# LP-IMP-P1_V3.net
KiCad netlist of a schematic drawn in EAGLE
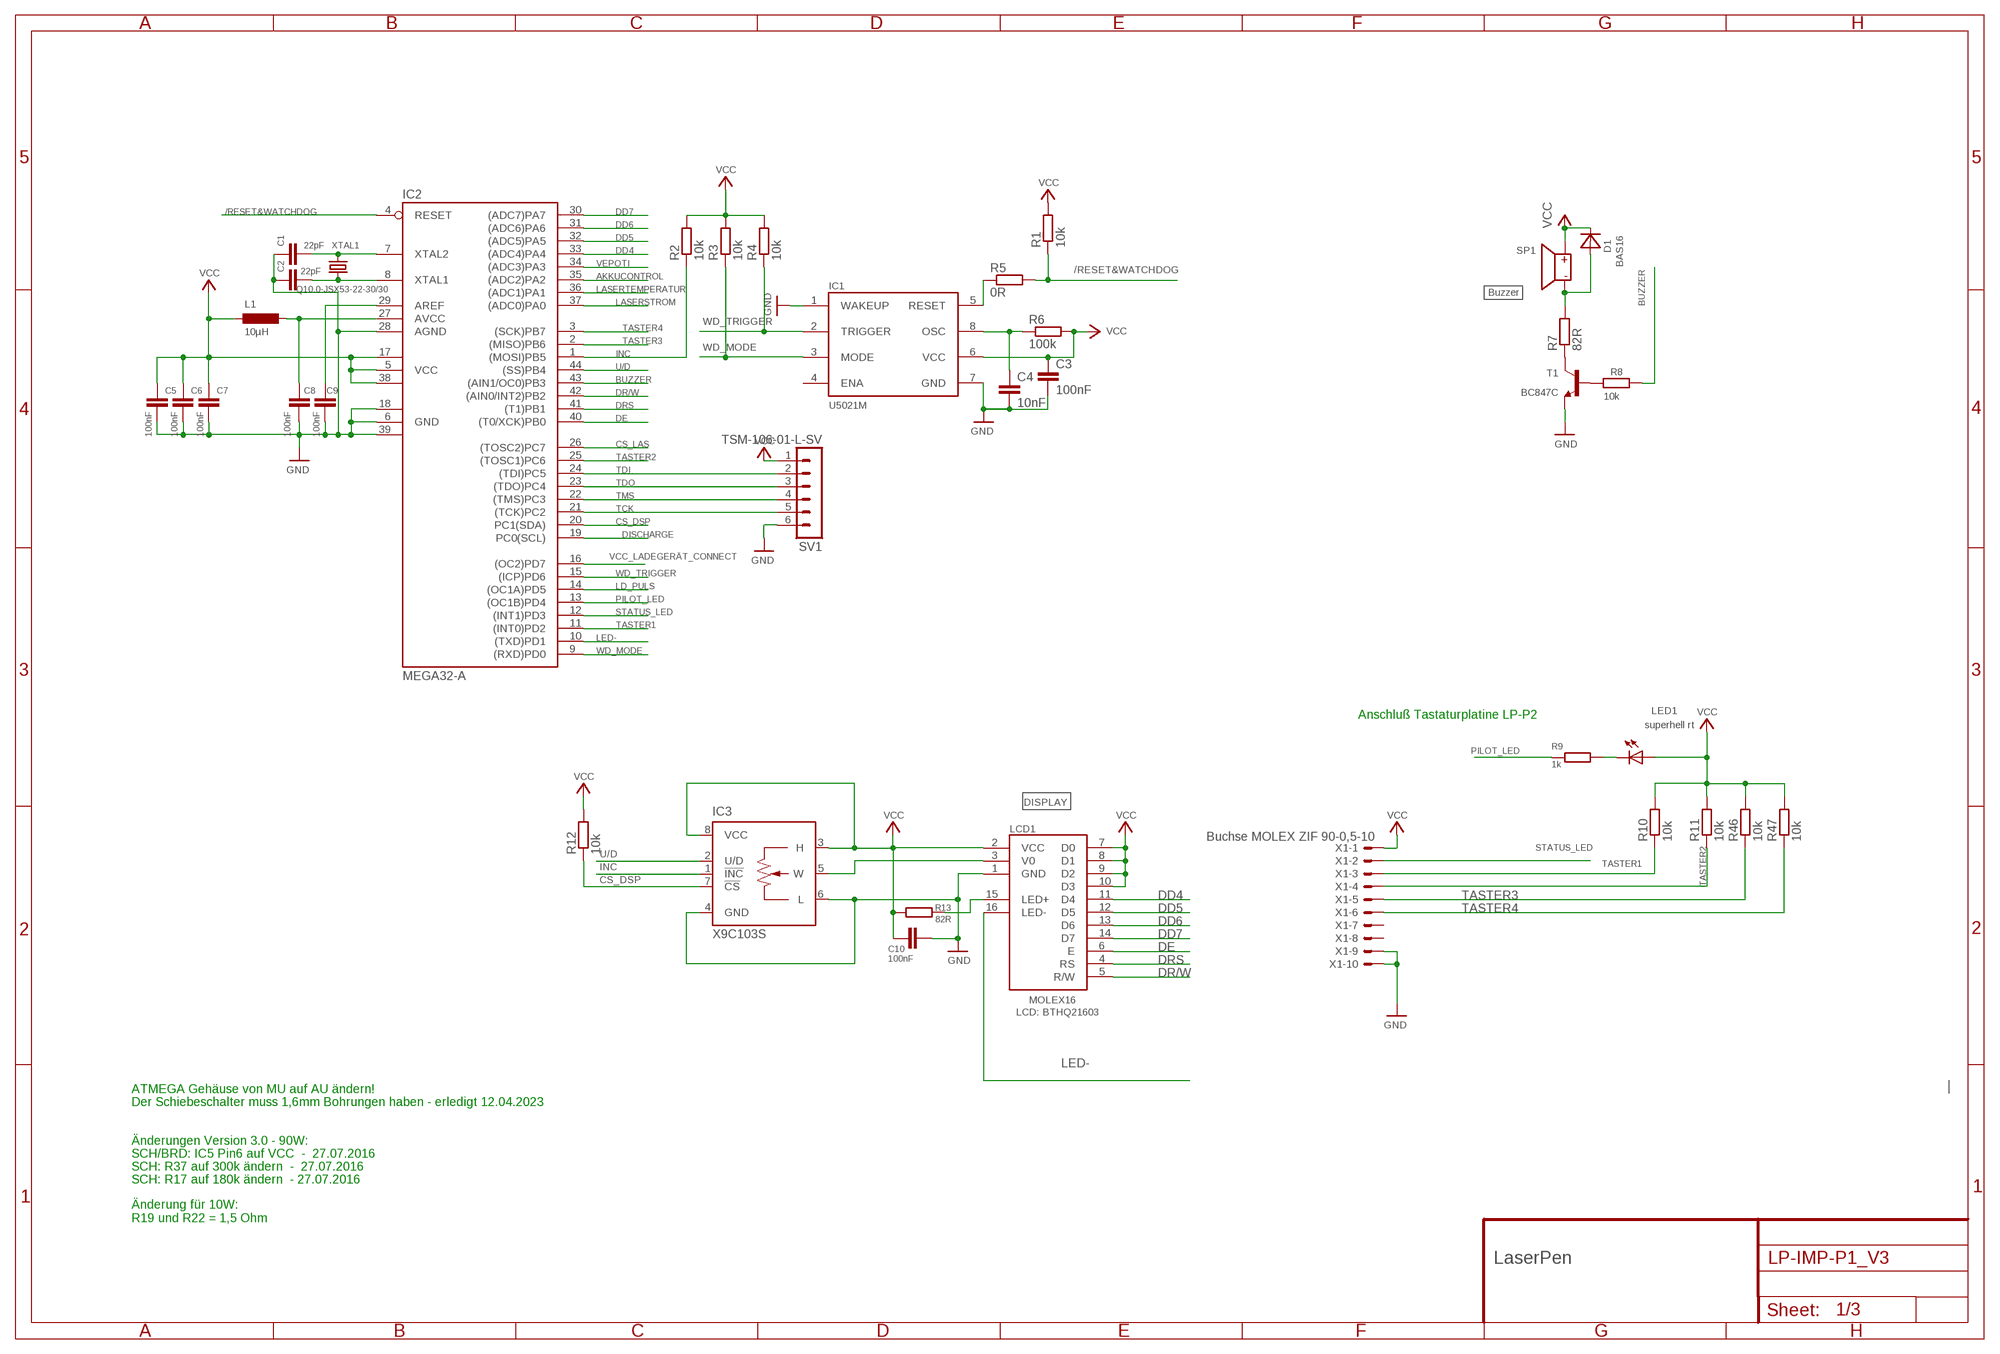
[diagram p0: schematic, sheet 1]
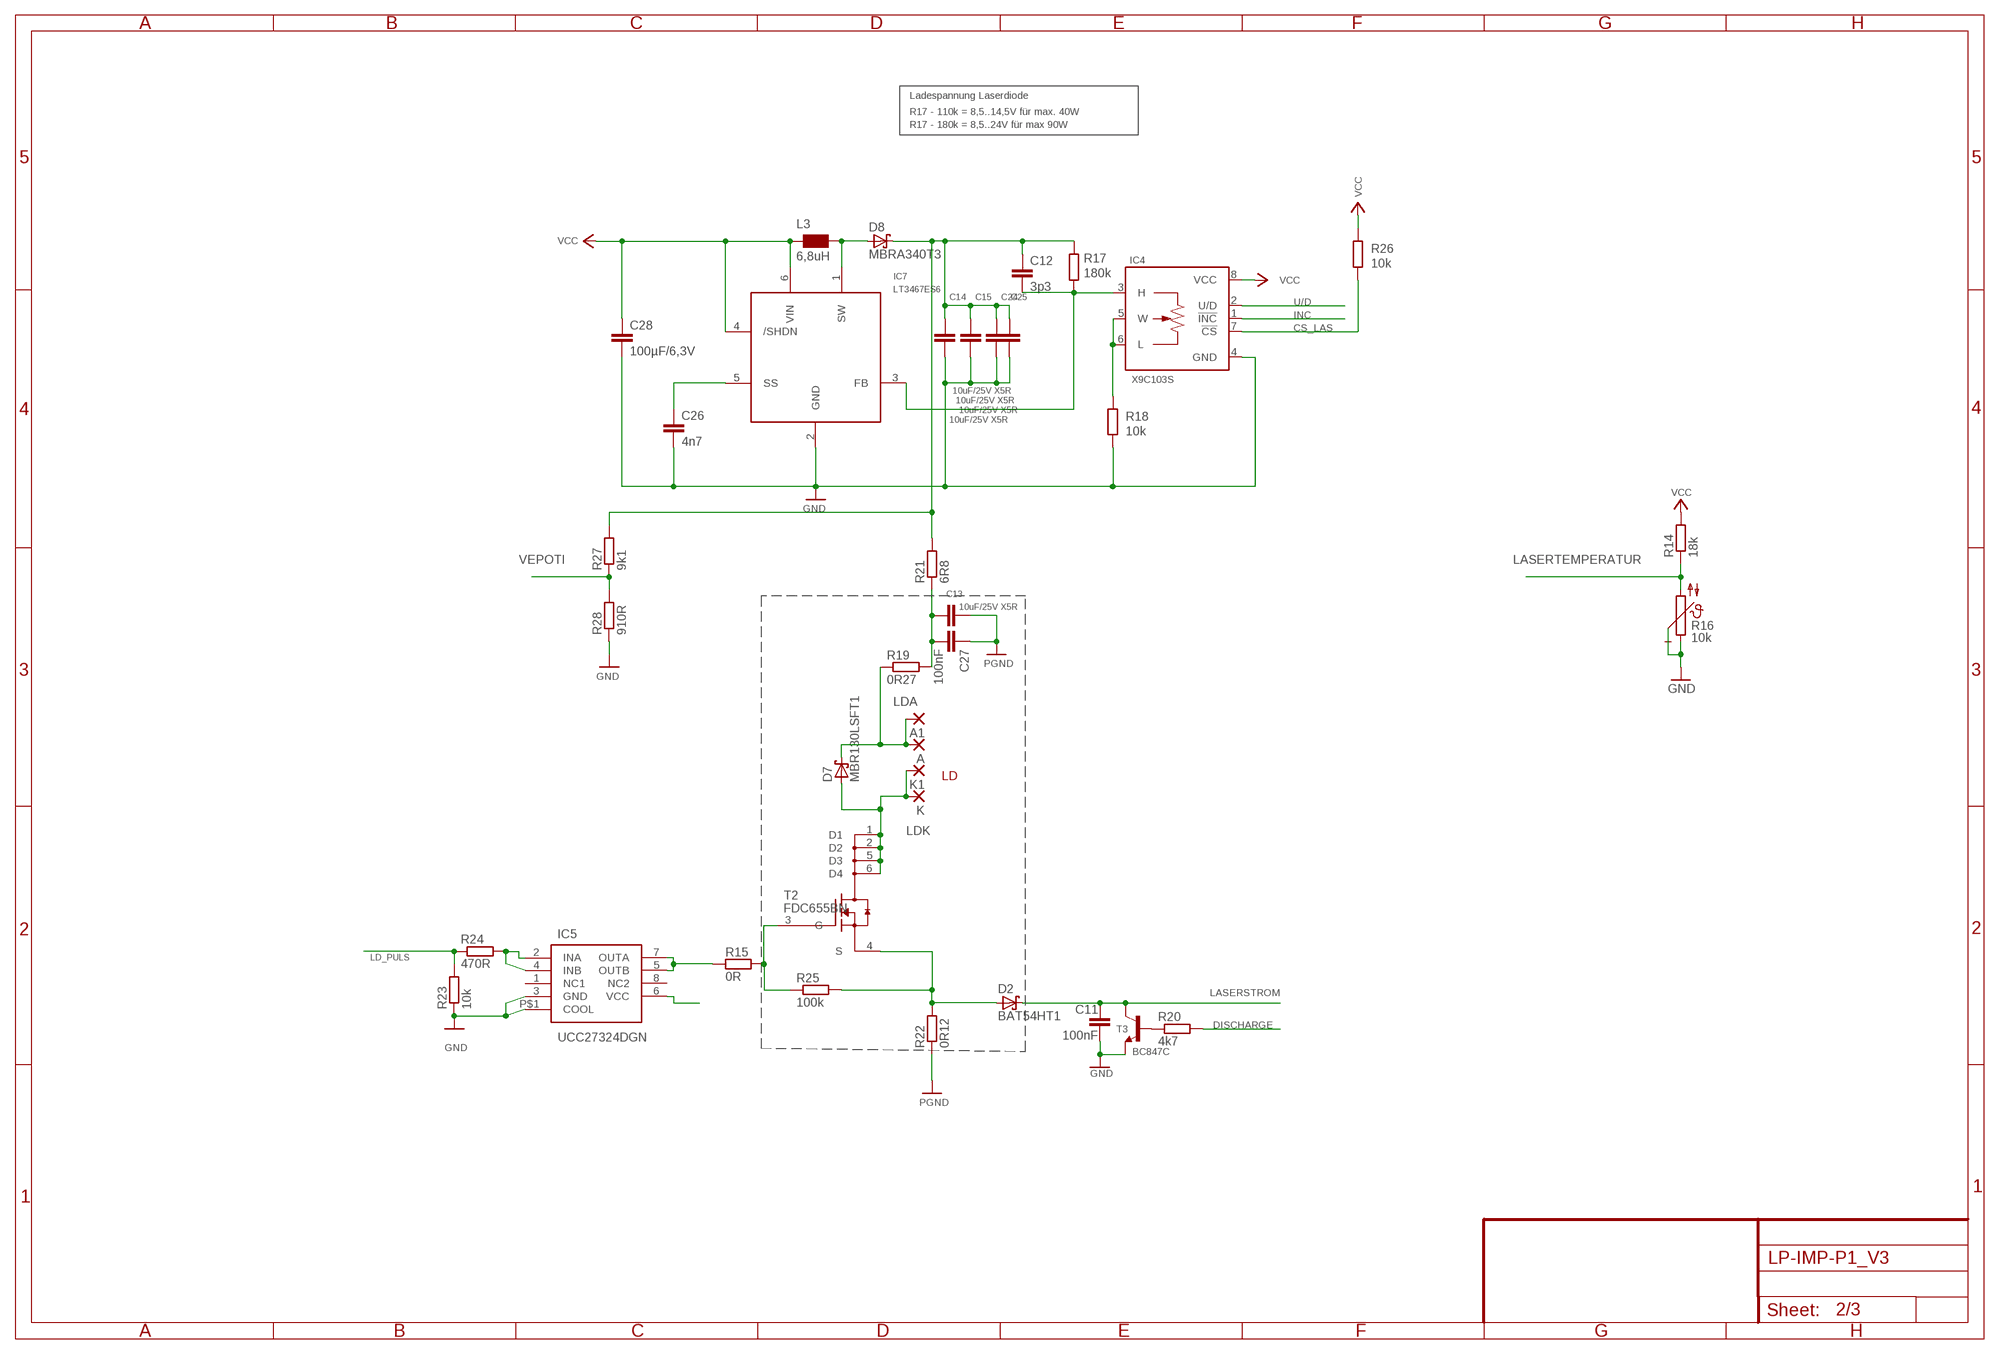
[diagram p1: schematic, sheet 2]
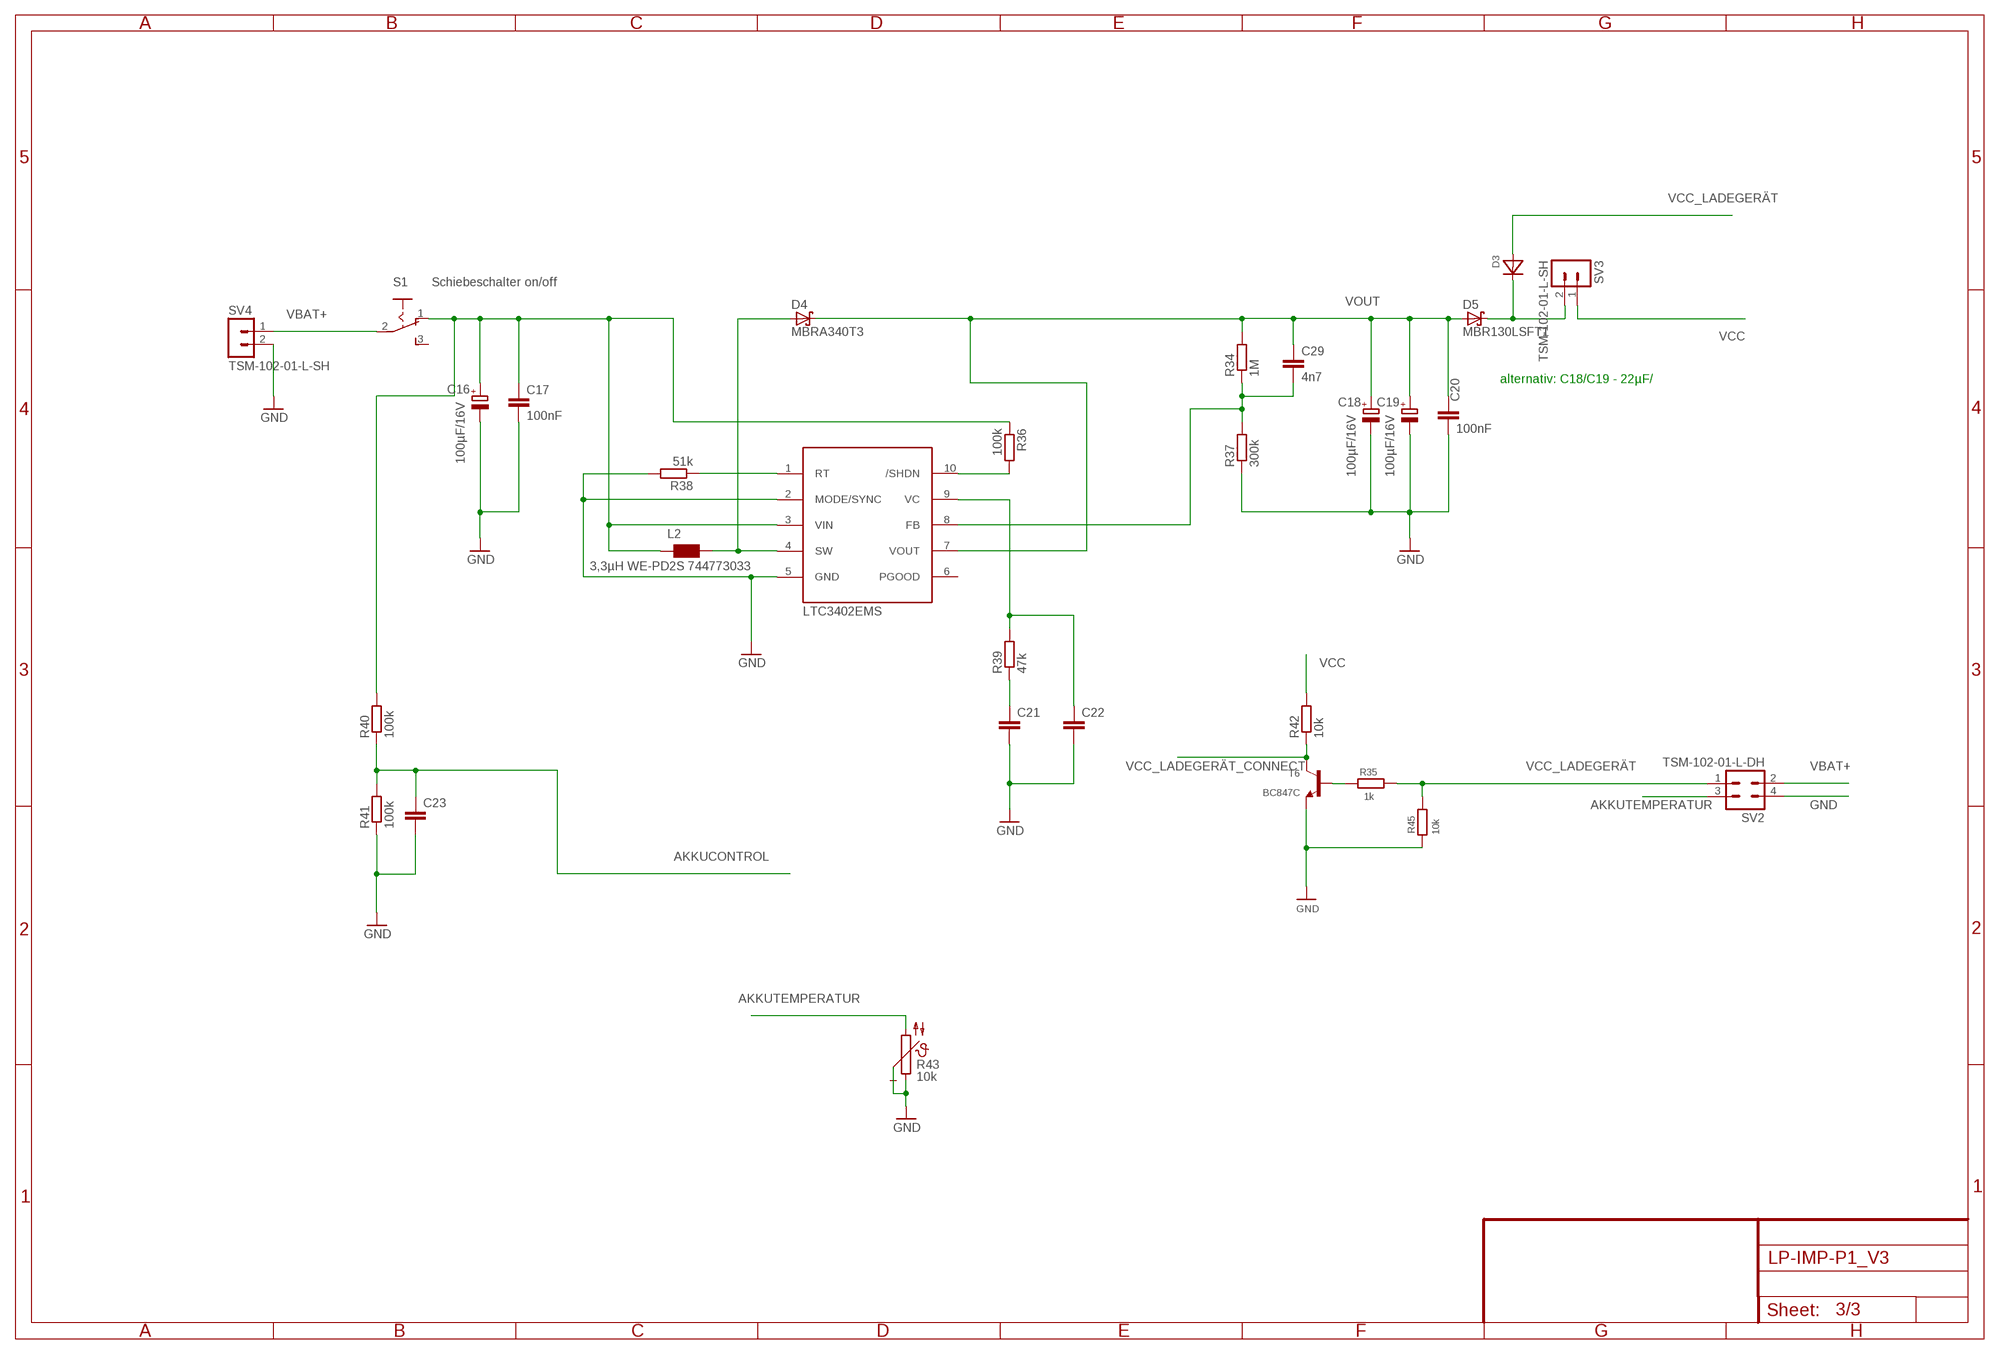
[diagram p2: schematic, sheet 3]

(export (version "E")
  (design (tool "Eeschema 10.0.6"))
  (components
    (comp (ref "A")
      (value "WIREPADSMD1,27-254")
      (footprint "eagle-import:SMD1,27-2,54")
      (libsource (lib "eagle-import") (part "WIREPADSMD1,27-254"))
    )
    (comp (ref "A1")
      (value "WIREPADSMD1,27-254")
      (footprint "eagle-import:SMD1,27-2,54")
      (libsource (lib "eagle-import") (part "WIREPADSMD1,27-254"))
    )
    (comp (ref "C11")
      (value "100nF")
      (footprint "eagle-import:C0603")
      (libsource (lib "eagle-import") (part "C-EUC0603"))
    )
    (comp (ref "C12")
      (value "3p3")
      (footprint "eagle-import:C0603")
      (libsource (lib "eagle-import") (part "C-EUC0603"))
    )
    (comp (ref "C13")
      (value "10uF/25V X5R")
      (footprint "eagle-import:C1210K")
      (libsource (lib "eagle-import") (part "C-EUC1210K"))
    )
    (comp (ref "C14")
      (value "10uF/25V X5R")
      (footprint "eagle-import:C1210K")
      (libsource (lib "eagle-import") (part "C-EUC1210K"))
    )
    (comp (ref "C15")
      (value "10uF/25V X5R")
      (footprint "eagle-import:C1210K")
      (libsource (lib "eagle-import") (part "C-EUC1210K"))
    )
    (comp (ref "C24")
      (value "10uF/25V X5R")
      (footprint "eagle-import:C1210K")
      (libsource (lib "eagle-import") (part "C-EUC1210K"))
    )
    (comp (ref "C25")
      (value "10uF/25V X5R")
      (footprint "eagle-import:C1210K")
      (libsource (lib "eagle-import") (part "C-EUC1210K"))
    )
    (comp (ref "C26")
      (value "4n7")
      (footprint "eagle-import:C0603K")
      (libsource (lib "eagle-import") (part "C-EUC0603K"))
    )
    (comp (ref "C27")
      (value "100nF")
      (footprint "eagle-import:C0603")
      (libsource (lib "eagle-import") (part "C-EUC0603"))
    )
    (comp (ref "C28")
      (value "100µF/6,3V")
      (footprint "eagle-import:C1210K")
      (libsource (lib "eagle-import") (part "C-EUC1210K"))
    )
    (comp (ref "D2")
      (value "BAT54HT1")
      (footprint "eagle-import:SOD-323")
      (libsource (lib "eagle-import") (part "BAT54HT1"))
    )
    (comp (ref "D7")
      (value "MBR130LSFT1")
      (footprint "eagle-import:SOD-123LF")
      (libsource (lib "eagle-import") (part "MBR130LSFT1"))
    )
    (comp (ref "D8")
      (value "MBRA340T3")
      (footprint "eagle-import:SMA")
      (libsource (lib "eagle-import") (part "pulslaser_MBRA340T3"))
    )
    (comp (ref "IC4")
      (value "X9C103S")
      (footprint "eagle-import:SOIC08")
      (libsource (lib "eagle-import") (part "X9C102S"))
    )
    (comp (ref "IC5")
      (value "UCC27324DGN")
      (footprint "eagle-import:R-PDSO-G8")
      (libsource (lib "eagle-import") (part "UCC27324DGN"))
    )
    (comp (ref "IC7")
      (value "LT3467ES6")
      (footprint "eagle-import:TSOT-23-6")
      (libsource (lib "eagle-import") (part "LT3467ES6"))
    )
    (comp (ref "K")
      (value "WIREPADSMD1,27-254")
      (footprint "eagle-import:SMD1,27-2,54")
      (libsource (lib "eagle-import") (part "WIREPADSMD1,27-254"))
    )
    (comp (ref "K1")
      (value "WIREPADSMD1,27-254")
      (footprint "eagle-import:SMD1,27-2,54")
      (libsource (lib "eagle-import") (part "WIREPADSMD1,27-254"))
    )
    (comp (ref "L3")
      (value "6,8uH")
      (footprint "eagle-import:WE-PD2_S")
      (libsource (lib "eagle-import") (part "WE-PD2_S"))
    )
    (comp (ref "R14")
      (value "18k")
      (footprint "eagle-import:R0603")
      (libsource (lib "eagle-import") (part "R-EU_R0603"))
    )
    (comp (ref "R15")
      (value "0R")
      (footprint "eagle-import:MINI_MELF-0204R")
      (libsource (lib "eagle-import") (part "R-EU_MELF0204R"))
    )
    (comp (ref "R16")
      (value "10k")
      (footprint "eagle-import:R0805")
      (libsource (lib "eagle-import") (part "NTC640SMD0805"))
    )
    (comp (ref "R17")
      (value "180k")
      (footprint "eagle-import:R0603")
      (libsource (lib "eagle-import") (part "R-EU_R0603"))
    )
    (comp (ref "R18")
      (value "10k")
      (footprint "eagle-import:R0603")
      (libsource (lib "eagle-import") (part "R-EU_R0603"))
    )
    (comp (ref "R19")
      (value "0R27")
      (footprint "eagle-import:MINI_MELF-0204R")
      (libsource (lib "eagle-import") (part "R-EU_MELF0204R"))
    )
    (comp (ref "R20")
      (value "4k7")
      (footprint "eagle-import:R0603")
      (libsource (lib "eagle-import") (part "R-EU_R0603"))
    )
    (comp (ref "R21")
      (value "6R8")
      (footprint "eagle-import:MINI_MELF-0204R")
      (libsource (lib "eagle-import") (part "R-EU_MELF0204R"))
    )
    (comp (ref "R22")
      (value "0R12")
      (footprint "eagle-import:MINI_MELF-0204R")
      (libsource (lib "eagle-import") (part "R-EU_MELF0204R"))
    )
    (comp (ref "R23")
      (value "10k")
      (footprint "eagle-import:R0603")
      (libsource (lib "eagle-import") (part "R-EU_R0603"))
    )
    (comp (ref "R24")
      (value "470R")
      (footprint "eagle-import:R0603")
      (libsource (lib "eagle-import") (part "R-EU_R0603"))
    )
    (comp (ref "R25")
      (value "100k")
      (footprint "eagle-import:R0603")
      (libsource (lib "eagle-import") (part "R-EU_R0603"))
    )
    (comp (ref "R26")
      (value "10k")
      (footprint "eagle-import:R0603")
      (libsource (lib "eagle-import") (part "R-EU_R0603"))
    )
    (comp (ref "R27")
      (value "9k1")
      (footprint "eagle-import:R0603")
      (libsource (lib "eagle-import") (part "R-EU_R0603"))
    )
    (comp (ref "R28")
      (value "910R")
      (footprint "eagle-import:R0603")
      (libsource (lib "eagle-import") (part "R-EU_R0603"))
    )
    (comp (ref "T2")
      (value "FDC655BN")
      (footprint "eagle-import:SUPERSOT-6")
      (libsource (lib "eagle-import") (part "FDC655BN"))
    )
    (comp (ref "T3")
      (value "BC847C")
      (footprint "eagle-import:SOT23-BEC")
      (libsource (lib "eagle-import") (part "BC849SMD"))
    )
    (comp (ref "C16")
      (value "100µF/16V")
      (footprint "eagle-import:SMC_D")
      (libsource (lib "eagle-import") (part "CPOL-EUSMCD"))
    )
    (comp (ref "C17")
      (value "100nF")
      (footprint "eagle-import:C0603K")
      (libsource (lib "eagle-import") (part "C-EUC0603K"))
    )
    (comp (ref "C18")
      (value "100µF/16V")
      (footprint "eagle-import:SMC_D")
      (libsource (lib "eagle-import") (part "CPOL-EUSMCD"))
    )
    (comp (ref "C19")
      (value "100µF/16V")
      (footprint "eagle-import:SMC_D")
      (libsource (lib "eagle-import") (part "CPOL-EUSMCD"))
    )
    (comp (ref "C20")
      (value "100nF")
      (footprint "eagle-import:C0603K")
      (libsource (lib "eagle-import") (part "C-EUC0603K"))
    )
    (comp (ref "C21")
      (value "1nF")
      (footprint "eagle-import:C0603K")
      (libsource (lib "eagle-import") (part "C-EUC0603K"))
    )
    (comp (ref "C22")
      (value "10pF")
      (footprint "eagle-import:C0603K")
      (libsource (lib "eagle-import") (part "C-EUC0603K"))
    )
    (comp (ref "C23")
      (value "100nF")
      (footprint "eagle-import:C0603K")
      (libsource (lib "eagle-import") (part "C-EUC0603K"))
    )
    (comp (ref "C29")
      (value "4n7")
      (footprint "eagle-import:C0603K")
      (libsource (lib "eagle-import") (part "C-EUC0603K"))
    )
    (comp (ref "D3")
      (value "BAS16")
      (footprint "eagle-import:DIODE_SOT23")
      (libsource (lib "eagle-import") (part "BAS16"))
    )
    (comp (ref "D4")
      (value "MBRA340T3")
      (footprint "eagle-import:SMA")
      (libsource (lib "eagle-import") (part "MBRA340T3"))
    )
    (comp (ref "D5")
      (value "MBR130LSFT1")
      (footprint "eagle-import:SOD-123LF")
      (libsource (lib "eagle-import") (part "MBR130LSFT1"))
    )
    (comp (ref "IC6")
      (value "LTC3402EMS")
      (footprint "eagle-import:MSOP-10")
      (libsource (lib "eagle-import") (part "LTC3402EMS"))
    )
    (comp (ref "L2")
      (value "3,3µH WE-PD2S 744773033")
      (footprint "eagle-import:WE-PD2_S")
      (libsource (lib "eagle-import") (part "wuerth-elektronik_EAGLE_v4_WE-PD2_S"))
    )
    (comp (ref "R34")
      (value "1M")
      (footprint "eagle-import:R0603")
      (libsource (lib "eagle-import") (part "R-EU_R0603"))
    )
    (comp (ref "R35")
      (value "1k")
      (footprint "eagle-import:R0603")
      (libsource (lib "eagle-import") (part "R-EU_R0603"))
    )
    (comp (ref "R36")
      (value "100k")
      (footprint "eagle-import:R0603")
      (libsource (lib "eagle-import") (part "R-EU_R0603"))
    )
    (comp (ref "R37")
      (value "300k")
      (footprint "eagle-import:R0603")
      (libsource (lib "eagle-import") (part "R-EU_R0603"))
    )
    (comp (ref "R38")
      (value "51k")
      (footprint "eagle-import:R0603")
      (libsource (lib "eagle-import") (part "R-EU_R0603"))
    )
    (comp (ref "R39")
      (value "47k")
      (footprint "eagle-import:R0603")
      (libsource (lib "eagle-import") (part "R-EU_R0603"))
    )
    (comp (ref "R40")
      (value "100k")
      (footprint "eagle-import:R0603")
      (libsource (lib "eagle-import") (part "R-EU_R0603"))
    )
    (comp (ref "R41")
      (value "100k")
      (footprint "eagle-import:R0603")
      (libsource (lib "eagle-import") (part "R-EU_R0603"))
    )
    (comp (ref "R42")
      (value "10k")
      (footprint "eagle-import:R0603")
      (libsource (lib "eagle-import") (part "R-EU_R0603"))
    )
    (comp (ref "R43")
      (value "10k")
      (footprint "eagle-import:R0805")
      (libsource (lib "eagle-import") (part "NTC640SMD0805"))
    )
    (comp (ref "R45")
      (value "10k")
      (footprint "eagle-import:R0603")
      (libsource (lib "eagle-import") (part "R-EU_R0603"))
    )
    (comp (ref "S1")
      (value "Schiebeschalter on/off")
      (footprint "eagle-import:255SB")
      (libsource (lib "eagle-import") (part "255SB"))
    )
    (comp (ref "SV2")
      (value "TSM-102-01-L-DH")
      (footprint "eagle-import:MA02-2-W-SMD")
      (libsource (lib "eagle-import") (part "MA02-2"))
    )
    (comp (ref "SV3")
      (value "TSM-102-01-L-SH")
      (footprint "eagle-import:MA02-1-W-SMD")
      (libsource (lib "eagle-import") (part "MA02-1W-SMD"))
    )
    (comp (ref "SV4")
      (value "TSM-102-01-L-SH")
      (footprint "eagle-import:MA02-1-W-SMD")
      (libsource (lib "eagle-import") (part "MA02-1W-SMD"))
    )
    (comp (ref "T6")
      (value "BC847C")
      (footprint "eagle-import:SOT23")
      (libsource (lib "eagle-import") (part "BC848"))
    )
    (comp (ref "C1")
      (value "22pF")
      (footprint "eagle-import:C0603")
      (libsource (lib "eagle-import") (part "C-EUC0603"))
    )
    (comp (ref "C2")
      (value "22pF")
      (footprint "eagle-import:C0603")
      (libsource (lib "eagle-import") (part "C-EUC0603"))
    )
    (comp (ref "C3")
      (value "100nF")
      (footprint "eagle-import:C0603")
      (libsource (lib "eagle-import") (part "C-EUC0603"))
    )
    (comp (ref "C4")
      (value "10nF")
      (footprint "eagle-import:C0603")
      (libsource (lib "eagle-import") (part "C-EUC0603"))
    )
    (comp (ref "C5")
      (value "100nF")
      (footprint "eagle-import:C0603")
      (libsource (lib "eagle-import") (part "C-EUC0603"))
    )
    (comp (ref "C6")
      (value "100nF")
      (footprint "eagle-import:C0603")
      (libsource (lib "eagle-import") (part "C-EUC0603"))
    )
    (comp (ref "C7")
      (value "100nF")
      (footprint "eagle-import:C0603")
      (libsource (lib "eagle-import") (part "C-EUC0603"))
    )
    (comp (ref "C8")
      (value "100nF")
      (footprint "eagle-import:C0603")
      (libsource (lib "eagle-import") (part "C-EUC0603"))
    )
    (comp (ref "C9")
      (value "100nF")
      (footprint "eagle-import:C0603")
      (libsource (lib "eagle-import") (part "C-EUC0603"))
    )
    (comp (ref "C10")
      (value "100nF")
      (footprint "eagle-import:C0603")
      (libsource (lib "eagle-import") (part "C-EUC0603"))
    )
    (comp (ref "D1")
      (value "BAS16")
      (footprint "eagle-import:DIODE_SOT23")
      (libsource (lib "eagle-import") (part "BAS16"))
    )
    (comp (ref "IC1")
      (value "U5021M")
      (footprint "eagle-import:SOIC8")
      (libsource (lib "eagle-import") (part "U5021M"))
    )
    (comp (ref "IC2")
      (value "MEGA32-A")
      (footprint "eagle-import:TQFP44")
      (libsource (lib "eagle-import") (part "MEGA32-A"))
    )
    (comp (ref "IC3")
      (value "X9C103S")
      (footprint "eagle-import:SOIC08")
      (libsource (lib "eagle-import") (part "X9C102S"))
    )
    (comp (ref "L1")
      (value "10µH")
      (footprint "eagle-import:R1210")
      (libsource (lib "eagle-import") (part "L-EU"))
    )
    (comp (ref "LCD1")
      (value "MOLEX16")
      (footprint "eagle-import:MOLEX")
      (libsource (lib "eagle-import") (part "LCD1"))
    )
    (comp (ref "LED1")
      (value "superhell rt")
      (footprint "eagle-import:LED3MM")
      (libsource (lib "eagle-import") (part "LED3MM"))
    )
    (comp (ref "R1")
      (value "10k")
      (footprint "eagle-import:R0603")
      (libsource (lib "eagle-import") (part "R-EU_R0603"))
    )
    (comp (ref "R2")
      (value "10k")
      (footprint "eagle-import:R0603")
      (libsource (lib "eagle-import") (part "R-EU_R0603"))
    )
    (comp (ref "R3")
      (value "10k")
      (footprint "eagle-import:R0603")
      (libsource (lib "eagle-import") (part "R-EU_R0603"))
    )
    (comp (ref "R4")
      (value "10k")
      (footprint "eagle-import:R0603")
      (libsource (lib "eagle-import") (part "R-EU_R0603"))
    )
    (comp (ref "R5")
      (value "0R")
      (footprint "eagle-import:R0603")
      (libsource (lib "eagle-import") (part "R-EU_R0603"))
    )
    (comp (ref "R6")
      (value "100k")
      (footprint "eagle-import:R0603")
      (libsource (lib "eagle-import") (part "R-EU_R0603"))
    )
    (comp (ref "R7")
      (value "82R")
      (footprint "eagle-import:MINI_MELF-0204R")
      (libsource (lib "eagle-import") (part "R-EU_MELF0204R"))
    )
    (comp (ref "R8")
      (value "10k")
      (footprint "eagle-import:R0603")
      (libsource (lib "eagle-import") (part "R-EU_R0603"))
    )
    (comp (ref "R9")
      (value "1k")
      (footprint "eagle-import:R0603")
      (libsource (lib "eagle-import") (part "R-EU_R0603"))
    )
    (comp (ref "R10")
      (value "10k")
      (footprint "eagle-import:R0603")
      (libsource (lib "eagle-import") (part "R-EU_R0603"))
    )
    (comp (ref "R11")
      (value "10k")
      (footprint "eagle-import:R0603")
      (libsource (lib "eagle-import") (part "R-EU_R0603"))
    )
    (comp (ref "R12")
      (value "10k")
      (footprint "eagle-import:R0603")
      (libsource (lib "eagle-import") (part "R-EU_R0603"))
    )
    (comp (ref "R13")
      (value "82R")
      (footprint "eagle-import:MINI_MELF-0204R")
      (libsource (lib "eagle-import") (part "R-EU_MELF0204R"))
    )
    (comp (ref "R46")
      (value "10k")
      (footprint "eagle-import:R0603")
      (libsource (lib "eagle-import") (part "R-EU_R0603"))
    )
    (comp (ref "R47")
      (value "10k")
      (footprint "eagle-import:R0603")
      (libsource (lib "eagle-import") (part "R-EU_R0603"))
    )
    (comp (ref "SP1")
      (value "BUZZERS")
      (footprint "eagle-import:BUZZER")
      (libsource (lib "eagle-import") (part "BUZZERS"))
    )
    (comp (ref "SV1")
      (value "TSM-106-01-L-SV")
      (footprint "eagle-import:MA06-1-SMD")
      (libsource (lib "eagle-import") (part "MA06-1MA06-1-SMD"))
    )
    (comp (ref "T1")
      (value "BC847C")
      (footprint "eagle-import:SOT23")
      (libsource (lib "eagle-import") (part "BC848"))
    )
    (comp (ref "X1")
      (value "Buchse MOLEX ZIF 90-0,5-10")
      (footprint "eagle-import:52745-1090")
      (libsource (lib "eagle-import") (part "53?-10"))
    )
    (comp (ref "XTAL1")
      (value "Q10.0-JSX53-22-30/30")
      (footprint "eagle-import:JSX53")
      (libsource (lib "eagle-import") (part "JSX53"))
    )
  )
  (nets
    (net (code "1") (name "AKKUCONTROL") (class "Default")
      (node (ref "C23") (pin "1") (pinfunction "1_1") (pintype "passive"))
      (node (ref "IC2") (pin "35") (pinfunction "(ADC2)PA2_35") (pintype "bidirectional"))
      (node (ref "R40") (pin "1") (pinfunction "1_1") (pintype "passive"))
      (node (ref "R41") (pin "2") (pinfunction "2_2") (pintype "passive"))
    )
    (net (code "2") (name "AKKUTEMPERATUR") (class "Default")
      (node (ref "R43") (pin "2") (pinfunction "2_2") (pintype "passive"))
      (node (ref "SV2") (pin "3") (pinfunction "3_3") (pintype "passive"))
    )
    (net (code "3") (name "BUZZER") (class "Default")
      (node (ref "IC2") (pin "43") (pinfunction "(AIN1/OC0)PB3_43") (pintype "bidirectional"))
      (node (ref "R8") (pin "1") (pinfunction "1_1") (pintype "passive"))
    )
    (net (code "4") (name "CS_DSP") (class "Default")
      (node (ref "IC2") (pin "20") (pinfunction "PC1(SDA)_20") (pintype "bidirectional"))
      (node (ref "IC3") (pin "7") (pinfunction "~{CS}_7") (pintype "input"))
      (node (ref "R12") (pin "1") (pinfunction "1_1") (pintype "passive"))
    )
    (net (code "5") (name "CS_LAS") (class "Default")
      (node (ref "IC2") (pin "26") (pinfunction "(TOSC2)PC7_26") (pintype "bidirectional"))
      (node (ref "IC4") (pin "7") (pinfunction "~{CS}_7") (pintype "input"))
      (node (ref "R26") (pin "1") (pinfunction "1_1") (pintype "passive"))
    )
    (net (code "6") (name "DD4") (class "Default")
      (node (ref "IC2") (pin "33") (pinfunction "(ADC4)PA4_33") (pintype "bidirectional"))
      (node (ref "LCD1") (pin "11") (pinfunction "D4_11") (pintype "bidirectional"))
    )
    (net (code "7") (name "DD5") (class "Default")
      (node (ref "IC2") (pin "32") (pinfunction "(ADC5)PA5_32") (pintype "bidirectional"))
      (node (ref "LCD1") (pin "12") (pinfunction "D5_12") (pintype "bidirectional"))
    )
    (net (code "8") (name "DD6") (class "Default")
      (node (ref "IC2") (pin "31") (pinfunction "(ADC6)PA6_31") (pintype "bidirectional"))
      (node (ref "LCD1") (pin "13") (pinfunction "D6_13") (pintype "bidirectional"))
    )
    (net (code "9") (name "DD7") (class "Default")
      (node (ref "IC2") (pin "30") (pinfunction "(ADC7)PA7_30") (pintype "bidirectional"))
      (node (ref "LCD1") (pin "14") (pinfunction "D7_14") (pintype "bidirectional"))
    )
    (net (code "10") (name "DE") (class "Default")
      (node (ref "IC2") (pin "40") (pinfunction "(T0/XCK)PB0_40") (pintype "bidirectional"))
      (node (ref "LCD1") (pin "6") (pinfunction "E_6") (pintype "input"))
    )
    (net (code "11") (name "DISCHARGE") (class "Default")
      (node (ref "IC2") (pin "19") (pinfunction "PC0(SCL)_19") (pintype "bidirectional"))
      (node (ref "R20") (pin "2") (pinfunction "2_2") (pintype "passive"))
    )
    (net (code "12") (name "DRS") (class "Default")
      (node (ref "IC2") (pin "41") (pinfunction "(T1)PB1_41") (pintype "bidirectional"))
      (node (ref "LCD1") (pin "4") (pinfunction "RS_4") (pintype "input"))
    )
    (net (code "13") (name "DR{slash}W") (class "Default")
      (node (ref "IC2") (pin "42") (pinfunction "(AIN0/INT2)PB2_42") (pintype "bidirectional"))
      (node (ref "LCD1") (pin "5") (pinfunction "R/W_5") (pintype "input"))
    )
    (net (code "14") (name "GND") (class "Default")
      (node (ref "C1") (pin "1") (pinfunction "1_1") (pintype "passive"))
      (node (ref "C10") (pin "1") (pinfunction "1_1") (pintype "passive"))
      (node (ref "C11") (pin "2") (pinfunction "2_2") (pintype "passive"))
      (node (ref "C13") (pin "2") (pinfunction "2_2") (pintype "passive"))
      (node (ref "C14") (pin "2") (pinfunction "2_2") (pintype "passive"))
      (node (ref "C15") (pin "2") (pinfunction "2_2") (pintype "passive"))
      (node (ref "C16") (pin "-") (pinfunction "-_-") (pintype "passive"))
      (node (ref "C17") (pin "2") (pinfunction "2_2") (pintype "passive"))
      (node (ref "C18") (pin "-") (pinfunction "-_-") (pintype "passive"))
      (node (ref "C19") (pin "-") (pinfunction "-_-") (pintype "passive"))
      (node (ref "C2") (pin "1") (pinfunction "1_1") (pintype "passive"))
      (node (ref "C20") (pin "2") (pinfunction "2_2") (pintype "passive"))
      (node (ref "C21") (pin "2") (pinfunction "2_2") (pintype "passive"))
      (node (ref "C22") (pin "2") (pinfunction "2_2") (pintype "passive"))
      (node (ref "C23") (pin "2") (pinfunction "2_2") (pintype "passive"))
      (node (ref "C24") (pin "2") (pinfunction "2_2") (pintype "passive"))
      (node (ref "C25") (pin "2") (pinfunction "2_2") (pintype "passive"))
      (node (ref "C26") (pin "2") (pinfunction "2_2") (pintype "passive"))
      (node (ref "C27") (pin "1") (pinfunction "1_1") (pintype "passive"))
      (node (ref "C28") (pin "2") (pinfunction "2_2") (pintype "passive"))
      (node (ref "C3") (pin "2") (pinfunction "2_2") (pintype "passive"))
      (node (ref "C4") (pin "2") (pinfunction "2_2") (pintype "passive"))
      (node (ref "C5") (pin "2") (pinfunction "2_2") (pintype "passive"))
      (node (ref "C6") (pin "2") (pinfunction "2_2") (pintype "passive"))
      (node (ref "C7") (pin "2") (pinfunction "2_2") (pintype "passive"))
      (node (ref "C8") (pin "2") (pinfunction "2_2") (pintype "passive"))
      (node (ref "C9") (pin "2") (pinfunction "2_2") (pintype "passive"))
      (node (ref "IC1") (pin "1") (pinfunction "WAKEUP_1") (pintype "bidirectional"))
      (node (ref "IC1") (pin "7") (pinfunction "GND_7") (pintype "bidirectional"))
      (node (ref "IC2") (pin "18") (pinfunction "GND1_18") (pintype "power_in"))
      (node (ref "IC2") (pin "28") (pinfunction "AGND_28") (pintype "power_in"))
      (node (ref "IC2") (pin "39") (pinfunction "GND2_39") (pintype "power_in"))
      (node (ref "IC2") (pin "6") (pinfunction "GND_6") (pintype "power_in"))
      (node (ref "IC3") (pin "4") (pinfunction "GND_4") (pintype "power_in"))
      (node (ref "IC3") (pin "6") (pinfunction "L_6") (pintype "passive"))
      (node (ref "IC4") (pin "4") (pinfunction "GND_4") (pintype "power_in"))
      (node (ref "IC5") (pin "3") (pinfunction "GND_3") (pintype "power_in"))
      (node (ref "IC5") (pin "P$1") (pinfunction "COOL_P$1") (pintype "passive"))
      (node (ref "IC6") (pin "2") (pinfunction "MODE/SYNC_2") (pintype "input"))
      (node (ref "IC6") (pin "5") (pinfunction "GND_5") (pintype "power_in"))
      (node (ref "IC7") (pin "2") (pinfunction "GND_2") (pintype "power_in"))
      (node (ref "LCD1") (pin "1") (pinfunction "GND_1") (pintype "power_in"))
      (node (ref "R16") (pin "1") (pinfunction "1_1") (pintype "passive"))
      (node (ref "R18") (pin "1") (pinfunction "1_1") (pintype "passive"))
      (node (ref "R22") (pin "1") (pinfunction "1_1") (pintype "passive"))
      (node (ref "R23") (pin "1") (pinfunction "1_1") (pintype "passive"))
      (node (ref "R28") (pin "1") (pinfunction "1_1") (pintype "passive"))
      (node (ref "R37") (pin "1") (pinfunction "1_1") (pintype "passive"))
      (node (ref "R38") (pin "2") (pinfunction "2_2") (pintype "passive"))
      (node (ref "R41") (pin "1") (pinfunction "1_1") (pintype "passive"))
      (node (ref "R43") (pin "1") (pinfunction "1_1") (pintype "passive"))
      (node (ref "R45") (pin "2") (pinfunction "2_2") (pintype "passive"))
      (node (ref "SV1") (pin "6") (pinfunction "6_6") (pintype "passive"))
      (node (ref "SV2") (pin "4") (pinfunction "4_4") (pintype "passive"))
      (node (ref "SV4") (pin "2") (pinfunction "2_2") (pintype "passive"))
      (node (ref "T1") (pin "2") (pinfunction "E_2") (pintype "passive"))
      (node (ref "T3") (pin "E") (pinfunction "E_E") (pintype "passive"))
      (node (ref "T6") (pin "2") (pinfunction "E_2") (pintype "passive"))
      (node (ref "X1") (pin "10") (pinfunction "S_10") (pintype "passive"))
      (node (ref "X1") (pin "9") (pinfunction "S_9") (pintype "passive"))
    )
    (net (code "15") (name "INC") (class "Default")
      (node (ref "IC2") (pin "1") (pinfunction "(MOSI)PB5_1") (pintype "bidirectional"))
      (node (ref "IC3") (pin "1") (pinfunction "~{INC}_1") (pintype "input"))
      (node (ref "IC4") (pin "1") (pinfunction "~{INC}_1") (pintype "input"))
      (node (ref "R2") (pin "1") (pinfunction "1_1") (pintype "passive"))
    )
    (net (code "16") (name "LASERSTROM") (class "Default")
      (node (ref "C11") (pin "1") (pinfunction "1_1") (pintype "passive"))
      (node (ref "D2") (pin "C") (pinfunction "C_C") (pintype "passive"))
      (node (ref "IC2") (pin "37") (pinfunction "(ADC0)PA0_37") (pintype "bidirectional"))
      (node (ref "T3") (pin "C") (pinfunction "C_C") (pintype "passive"))
    )
    (net (code "17") (name "LASERTEMPERATUR") (class "Default")
      (node (ref "IC2") (pin "36") (pinfunction "(ADC1)PA1_36") (pintype "bidirectional"))
      (node (ref "R14") (pin "1") (pinfunction "1_1") (pintype "passive"))
      (node (ref "R16") (pin "2") (pinfunction "2_2") (pintype "passive"))
    )
    (net (code "18") (name "LDA") (class "Default")
      (node (ref "A") (pin "1") (pinfunction "P_1") (pintype "passive"))
      (node (ref "A1") (pin "1") (pinfunction "P_1") (pintype "passive"))
      (node (ref "D7") (pin "C") (pinfunction "C_C") (pintype "passive"))
      (node (ref "R19") (pin "1") (pinfunction "1_1") (pintype "passive"))
    )
    (net (code "19") (name "LDK") (class "Default")
      (node (ref "D7") (pin "A") (pinfunction "A_A") (pintype "passive"))
      (node (ref "K") (pin "1") (pinfunction "P_1") (pintype "passive"))
      (node (ref "K1") (pin "1") (pinfunction "P_1") (pintype "passive"))
      (node (ref "T2") (pin "1") (pinfunction "D1_1") (pintype "passive"))
      (node (ref "T2") (pin "2") (pinfunction "D2_2") (pintype "passive"))
      (node (ref "T2") (pin "5") (pinfunction "D3_5") (pintype "passive"))
      (node (ref "T2") (pin "6") (pinfunction "D4_6") (pintype "passive"))
    )
    (net (code "20") (name "LD_PULS") (class "Default")
      (node (ref "IC2") (pin "14") (pinfunction "(OC1A)PD5_14") (pintype "bidirectional"))
      (node (ref "R23") (pin "2") (pinfunction "2_2") (pintype "passive"))
      (node (ref "R24") (pin "1") (pinfunction "1_1") (pintype "passive"))
    )
    (net (code "21") (name "LED-") (class "Default")
      (node (ref "IC2") (pin "10") (pinfunction "(TXD)PD1_10") (pintype "bidirectional"))
      (node (ref "LCD1") (pin "16") (pinfunction "LED-_16") (pintype "power_in"))
    )
    (net (code "22") (name "Net-(C12-Pad1)") (class "Default")
      (node (ref "C12") (pin "1") (pinfunction "1_1") (pintype "passive"))
      (node (ref "C14") (pin "1") (pinfunction "1_1") (pintype "passive"))
      (node (ref "C15") (pin "1") (pinfunction "1_1") (pintype "passive"))
      (node (ref "C24") (pin "1") (pinfunction "1_1") (pintype "passive"))
      (node (ref "C25") (pin "1") (pinfunction "1_1") (pintype "passive"))
      (node (ref "D8") (pin "C") (pinfunction "C_C") (pintype "passive"))
      (node (ref "R17") (pin "2") (pinfunction "2_2") (pintype "passive"))
      (node (ref "R21") (pin "2") (pinfunction "2_2") (pintype "passive"))
      (node (ref "R27") (pin "2") (pinfunction "2_2") (pintype "passive"))
    )
    (net (code "23") (name "Net-(C13-Pad1)") (class "Default")
      (node (ref "C13") (pin "1") (pinfunction "1_1") (pintype "passive"))
      (node (ref "C27") (pin "2") (pinfunction "2_2") (pintype "passive"))
      (node (ref "R19") (pin "2") (pinfunction "2_2") (pintype "passive"))
      (node (ref "R21") (pin "1") (pinfunction "1_1") (pintype "passive"))
    )
    (net (code "24") (name "Net-(C21-Pad1)") (class "Default")
      (node (ref "C21") (pin "1") (pinfunction "1_1") (pintype "passive"))
      (node (ref "R39") (pin "1") (pinfunction "1_1") (pintype "passive"))
    )
    (net (code "25") (name "Net-(D1-A)") (class "Default")
      (node (ref "D1") (pin "1") (pinfunction "A_1") (pintype "passive"))
      (node (ref "R7") (pin "2") (pinfunction "2_2") (pintype "passive"))
      (node (ref "SP1") (pin "-") (pinfunction "-_-") (pintype "passive"))
    )
    (net (code "26") (name "Net-(D3-C)") (class "Default")
      (node (ref "D3") (pin "3") (pinfunction "C_3") (pintype "passive"))
      (node (ref "D5") (pin "C") (pinfunction "C_C") (pintype "passive"))
      (node (ref "SV3") (pin "2") (pinfunction "2_2") (pintype "passive"))
    )
    (net (code "27") (name "Net-(IC1-OSC)") (class "Default")
      (node (ref "C4") (pin "1") (pinfunction "1_1") (pintype "passive"))
      (node (ref "IC1") (pin "8") (pinfunction "OSC_8") (pintype "bidirectional"))
      (node (ref "R6") (pin "1") (pinfunction "1_1") (pintype "passive"))
    )
    (net (code "28") (name "Net-(IC1-RESET)") (class "Default")
      (node (ref "IC1") (pin "5") (pinfunction "RESET_5") (pintype "bidirectional"))
      (node (ref "R5") (pin "1") (pinfunction "1_1") (pintype "passive"))
    )
    (net (code "29") (name "Net-(IC2-AREF)") (class "Default")
      (node (ref "C9") (pin "1") (pinfunction "1_1") (pintype "passive"))
      (node (ref "IC2") (pin "29") (pinfunction "AREF_29") (pintype "power_in"))
    )
    (net (code "30") (name "Net-(IC2-AVCC)") (class "Default")
      (node (ref "C8") (pin "1") (pinfunction "1_1") (pintype "passive"))
      (node (ref "IC2") (pin "27") (pinfunction "AVCC_27") (pintype "power_in"))
      (node (ref "L1") (pin "1") (pinfunction "1_1") (pintype "passive"))
    )
    (net (code "31") (name "Net-(IC2-XTAL1)") (class "Default")
      (node (ref "C2") (pin "2") (pinfunction "2_2") (pintype "passive"))
      (node (ref "IC2") (pin "8") (pinfunction "XTAL1_8") (pintype "bidirectional"))
      (node (ref "XTAL1") (pin "1") (pinfunction "1_1") (pintype "passive"))
    )
    (net (code "32") (name "Net-(IC2-XTAL2)") (class "Default")
      (node (ref "C1") (pin "2") (pinfunction "2_2") (pintype "passive"))
      (node (ref "IC2") (pin "7") (pinfunction "XTAL2_7") (pintype "bidirectional"))
      (node (ref "XTAL1") (pin "3") (pinfunction "2_3") (pintype "passive"))
    )
    (net (code "33") (name "Net-(IC3-W)") (class "Default")
      (node (ref "IC3") (pin "5") (pinfunction "W_5") (pintype "passive"))
      (node (ref "LCD1") (pin "3") (pinfunction "V0_3") (pintype "power_in"))
    )
    (net (code "34") (name "Net-(IC4-H)") (class "Default")
      (node (ref "C12") (pin "2") (pinfunction "2_2") (pintype "passive"))
      (node (ref "IC4") (pin "3") (pinfunction "H_3") (pintype "passive"))
      (node (ref "IC7") (pin "3") (pinfunction "FB_3") (pintype "passive"))
      (node (ref "R17") (pin "1") (pinfunction "1_1") (pintype "passive"))
    )
    (net (code "35") (name "Net-(IC4-L)") (class "Default")
      (node (ref "IC4") (pin "5") (pinfunction "W_5") (pintype "passive"))
      (node (ref "IC4") (pin "6") (pinfunction "L_6") (pintype "passive"))
      (node (ref "R18") (pin "2") (pinfunction "2_2") (pintype "passive"))
    )
    (net (code "36") (name "Net-(IC5-INA)") (class "Default")
      (node (ref "IC5") (pin "2") (pinfunction "INA_2") (pintype "input"))
      (node (ref "IC5") (pin "4") (pinfunction "INB_4") (pintype "input"))
      (node (ref "R24") (pin "2") (pinfunction "2_2") (pintype "passive"))
    )
    (net (code "37") (name "Net-(IC5-OUTA)") (class "Default")
      (node (ref "IC5") (pin "5") (pinfunction "OUTB_5") (pintype "output"))
      (node (ref "IC5") (pin "7") (pinfunction "OUTA_7") (pintype "output"))
      (node (ref "R15") (pin "1") (pinfunction "1_1") (pintype "passive"))
    )
    (net (code "38") (name "Net-(IC6-FB)") (class "Default")
      (node (ref "C29") (pin "2") (pinfunction "2_2") (pintype "passive"))
      (node (ref "IC6") (pin "8") (pinfunction "FB_8") (pintype "passive"))
      (node (ref "R34") (pin "1") (pinfunction "1_1") (pintype "passive"))
      (node (ref "R37") (pin "2") (pinfunction "2_2") (pintype "passive"))
    )
    (net (code "39") (name "Net-(IC6-RT)") (class "Default")
      (node (ref "IC6") (pin "1") (pinfunction "RT_1") (pintype "passive"))
      (node (ref "R38") (pin "1") (pinfunction "1_1") (pintype "passive"))
    )
    (net (code "40") (name "Net-(IC6-SW)") (class "Default")
      (node (ref "D4") (pin "A") (pinfunction "A_A") (pintype "passive"))
      (node (ref "IC6") (pin "4") (pinfunction "SW_4") (pintype "passive"))
      (node (ref "L2") (pin "1") (pinfunction "2_1") (pintype "passive"))
    )
    (net (code "41") (name "Net-(IC6-VC)") (class "Default")
      (node (ref "C22") (pin "1") (pinfunction "1_1") (pintype "passive"))
      (node (ref "IC6") (pin "9") (pinfunction "VC_9") (pintype "passive"))
      (node (ref "R39") (pin "2") (pinfunction "2_2") (pintype "passive"))
    )
    (net (code "42") (name "Net-(IC6-VIN)") (class "Default")
      (node (ref "C16") (pin "+") (pinfunction "+_+") (pintype "passive"))
      (node (ref "C17") (pin "1") (pinfunction "1_1") (pintype "passive"))
      (node (ref "IC6") (pin "3") (pinfunction "VIN_3") (pintype "power_in"))
      (node (ref "L2") (pin "2") (pinfunction "1_2") (pintype "passive"))
      (node (ref "R36") (pin "1") (pinfunction "1_1") (pintype "passive"))
      (node (ref "R40") (pin "2") (pinfunction "2_2") (pintype "passive"))
      (node (ref "S1") (pin "1") (pinfunction "O_1") (pintype "passive"))
    )
    (net (code "43") (name "Net-(IC6-{slash}SHDN)") (class "Default")
      (node (ref "IC6") (pin "10") (pinfunction "/SHDN_10") (pintype "input"))
      (node (ref "R36") (pin "2") (pinfunction "2_2") (pintype "passive"))
    )
    (net (code "44") (name "Net-(IC7-SS)") (class "Default")
      (node (ref "C26") (pin "1") (pinfunction "1_1") (pintype "passive"))
      (node (ref "IC7") (pin "5") (pinfunction "SS_5") (pintype "passive"))
    )
    (net (code "45") (name "Net-(IC7-SW)") (class "Default")
      (node (ref "D8") (pin "A") (pinfunction "A_A") (pintype "passive"))
      (node (ref "IC7") (pin "1") (pinfunction "SW_1") (pintype "passive"))
      (node (ref "L3") (pin "1") (pinfunction "2_1") (pintype "passive"))
    )
    (net (code "46") (name "Net-(LCD1-LED+)") (class "Default")
      (node (ref "LCD1") (pin "15") (pinfunction "LED+_15") (pintype "power_in"))
      (node (ref "R13") (pin "2") (pinfunction "2_2") (pintype "passive"))
    )
    (net (code "47") (name "Net-(LED1-C)") (class "Default")
      (node (ref "LED1") (pin "K") (pinfunction "C_K") (pintype "passive"))
      (node (ref "R9") (pin "2") (pinfunction "2_2") (pintype "passive"))
    )
    (net (code "48") (name "Net-(R20-Pad1)") (class "Default")
      (node (ref "R20") (pin "1") (pinfunction "1_1") (pintype "passive"))
      (node (ref "T3") (pin "B") (pinfunction "B_B") (pintype "passive"))
    )
    (net (code "49") (name "Net-(T1-B)") (class "Default")
      (node (ref "R8") (pin "2") (pinfunction "2_2") (pintype "passive"))
      (node (ref "T1") (pin "1") (pinfunction "B_1") (pintype "passive"))
    )
    (net (code "50") (name "Net-(T1-C)") (class "Default")
      (node (ref "R7") (pin "1") (pinfunction "1_1") (pintype "passive"))
      (node (ref "T1") (pin "3") (pinfunction "C_3") (pintype "passive"))
    )
    (net (code "51") (name "Net-(T2-G)") (class "Default")
      (node (ref "R15") (pin "2") (pinfunction "2_2") (pintype "passive"))
      (node (ref "R25") (pin "1") (pinfunction "1_1") (pintype "passive"))
      (node (ref "T2") (pin "3") (pinfunction "G_3") (pintype "passive"))
    )
    (net (code "52") (name "Net-(T2-S)") (class "Default")
      (node (ref "D2") (pin "A") (pinfunction "A_A") (pintype "passive"))
      (node (ref "R22") (pin "2") (pinfunction "2_2") (pintype "passive"))
      (node (ref "R25") (pin "2") (pinfunction "2_2") (pintype "passive"))
      (node (ref "T2") (pin "4") (pinfunction "S_4") (pintype "passive"))
    )
    (net (code "53") (name "Net-(T6-B)") (class "Default")
      (node (ref "R35") (pin "2") (pinfunction "2_2") (pintype "passive"))
      (node (ref "T6") (pin "1") (pinfunction "B_1") (pintype "passive"))
    )
    (net (code "54") (name "PILOT_LED") (class "Default")
      (node (ref "IC2") (pin "13") (pinfunction "(OC1B)PD4_13") (pintype "bidirectional"))
      (node (ref "R9") (pin "1") (pinfunction "1_1") (pintype "passive"))
    )
    (net (code "55") (name "STATUS_LED") (class "Default")
      (node (ref "IC2") (pin "12") (pinfunction "(INT1)PD3_12") (pintype "bidirectional"))
      (node (ref "X1") (pin "2") (pinfunction "S_2") (pintype "passive"))
    )
    (net (code "56") (name "TASTER1") (class "Default")
      (node (ref "IC2") (pin "11") (pinfunction "(INT0)PD2_11") (pintype "bidirectional"))
      (node (ref "R10") (pin "1") (pinfunction "1_1") (pintype "passive"))
      (node (ref "X1") (pin "3") (pinfunction "S_3") (pintype "passive"))
    )
    (net (code "57") (name "TASTER2") (class "Default")
      (node (ref "IC2") (pin "25") (pinfunction "(TOSC1)PC6_25") (pintype "bidirectional"))
      (node (ref "R11") (pin "1") (pinfunction "1_1") (pintype "passive"))
      (node (ref "X1") (pin "4") (pinfunction "S_4") (pintype "passive"))
    )
    (net (code "58") (name "TASTER3") (class "Default")
      (node (ref "IC2") (pin "2") (pinfunction "(MISO)PB6_2") (pintype "bidirectional"))
      (node (ref "R46") (pin "1") (pinfunction "1_1") (pintype "passive"))
      (node (ref "X1") (pin "5") (pinfunction "S_5") (pintype "passive"))
    )
    (net (code "59") (name "TASTER4") (class "Default")
      (node (ref "IC2") (pin "3") (pinfunction "(SCK)PB7_3") (pintype "bidirectional"))
      (node (ref "R47") (pin "1") (pinfunction "1_1") (pintype "passive"))
      (node (ref "X1") (pin "6") (pinfunction "S_6") (pintype "passive"))
    )
    (net (code "60") (name "TCK") (class "Default")
      (node (ref "IC2") (pin "21") (pinfunction "(TCK)PC2_21") (pintype "bidirectional"))
      (node (ref "SV1") (pin "5") (pinfunction "5_5") (pintype "passive"))
    )
    (net (code "61") (name "TDI") (class "Default")
      (node (ref "IC2") (pin "24") (pinfunction "(TDI)PC5_24") (pintype "bidirectional"))
      (node (ref "SV1") (pin "2") (pinfunction "2_2") (pintype "passive"))
    )
    (net (code "62") (name "TDO") (class "Default")
      (node (ref "IC2") (pin "23") (pinfunction "(TDO)PC4_23") (pintype "bidirectional"))
      (node (ref "SV1") (pin "3") (pinfunction "3_3") (pintype "passive"))
    )
    (net (code "63") (name "TMS") (class "Default")
      (node (ref "IC2") (pin "22") (pinfunction "(TMS)PC3_22") (pintype "bidirectional"))
      (node (ref "SV1") (pin "4") (pinfunction "4_4") (pintype "passive"))
    )
    (net (code "64") (name "U{slash}D") (class "Default")
      (node (ref "IC2") (pin "44") (pinfunction "(SS)PB4_44") (pintype "bidirectional"))
      (node (ref "IC3") (pin "2") (pinfunction "U/D_2") (pintype "input"))
      (node (ref "IC4") (pin "2") (pinfunction "U/D_2") (pintype "input"))
    )
    (net (code "65") (name "VBAT+") (class "Default")
      (node (ref "S1") (pin "2") (pinfunction "P_2") (pintype "passive"))
      (node (ref "SV2") (pin "2") (pinfunction "2_2") (pintype "passive"))
      (node (ref "SV4") (pin "1") (pinfunction "1_1") (pintype "passive"))
    )
    (net (code "66") (name "VCC") (class "Default")
      (node (ref "C10") (pin "2") (pinfunction "2_2") (pintype "passive"))
      (node (ref "C28") (pin "1") (pinfunction "1_1") (pintype "passive"))
      (node (ref "C3") (pin "1") (pinfunction "1_1") (pintype "passive"))
      (node (ref "C5") (pin "1") (pinfunction "1_1") (pintype "passive"))
      (node (ref "C6") (pin "1") (pinfunction "1_1") (pintype "passive"))
      (node (ref "C7") (pin "1") (pinfunction "1_1") (pintype "passive"))
      (node (ref "D1") (pin "3") (pinfunction "C_3") (pintype "passive"))
      (node (ref "IC1") (pin "6") (pinfunction "VCC_6") (pintype "bidirectional"))
      (node (ref "IC2") (pin "17") (pinfunction "VCC1_17") (pintype "power_in"))
      (node (ref "IC2") (pin "38") (pinfunction "VCC2_38") (pintype "power_in"))
      (node (ref "IC2") (pin "5") (pinfunction "VCC_5") (pintype "power_in"))
      (node (ref "IC3") (pin "3") (pinfunction "H_3") (pintype "passive"))
      (node (ref "IC3") (pin "8") (pinfunction "VCC_8") (pintype "power_in"))
      (node (ref "IC4") (pin "8") (pinfunction "VCC_8") (pintype "power_in"))
      (node (ref "IC5") (pin "6") (pinfunction "VCC_6") (pintype "power_in"))
      (node (ref "IC7") (pin "4") (pinfunction "/SHDN_4") (pintype "input"))
      (node (ref "IC7") (pin "6") (pinfunction "VIN_6") (pintype "power_in"))
      (node (ref "L1") (pin "2") (pinfunction "2_2") (pintype "passive"))
      (node (ref "L3") (pin "2") (pinfunction "1_2") (pintype "passive"))
      (node (ref "LCD1") (pin "10") (pinfunction "D3_10") (pintype "bidirectional"))
      (node (ref "LCD1") (pin "2") (pinfunction "VCC_2") (pintype "power_in"))
      (node (ref "LCD1") (pin "7") (pinfunction "D0_7") (pintype "bidirectional"))
      (node (ref "LCD1") (pin "8") (pinfunction "D1_8") (pintype "bidirectional"))
      (node (ref "LCD1") (pin "9") (pinfunction "D2_9") (pintype "bidirectional"))
      (node (ref "LED1") (pin "A") (pinfunction "A_A") (pintype "passive"))
      (node (ref "R1") (pin "2") (pinfunction "2_2") (pintype "passive"))
      (node (ref "R10") (pin "2") (pinfunction "2_2") (pintype "passive"))
      (node (ref "R11") (pin "2") (pinfunction "2_2") (pintype "passive"))
      (node (ref "R12") (pin "2") (pinfunction "2_2") (pintype "passive"))
      (node (ref "R13") (pin "1") (pinfunction "1_1") (pintype "passive"))
      (node (ref "R14") (pin "2") (pinfunction "2_2") (pintype "passive"))
      (node (ref "R2") (pin "2") (pinfunction "2_2") (pintype "passive"))
      (node (ref "R26") (pin "2") (pinfunction "2_2") (pintype "passive"))
      (node (ref "R3") (pin "2") (pinfunction "2_2") (pintype "passive"))
      (node (ref "R4") (pin "2") (pinfunction "2_2") (pintype "passive"))
      (node (ref "R42") (pin "2") (pinfunction "2_2") (pintype "passive"))
      (node (ref "R46") (pin "2") (pinfunction "2_2") (pintype "passive"))
      (node (ref "R47") (pin "2") (pinfunction "2_2") (pintype "passive"))
      (node (ref "R6") (pin "2") (pinfunction "2_2") (pintype "passive"))
      (node (ref "SP1") (pin "+") (pinfunction "+_+") (pintype "passive"))
      (node (ref "SV1") (pin "1") (pinfunction "1_1") (pintype "passive"))
      (node (ref "SV3") (pin "1") (pinfunction "1_1") (pintype "passive"))
      (node (ref "X1") (pin "1") (pinfunction "S_1") (pintype "passive"))
    )
    (net (code "67") (name "VCC_LADEGERÄT") (class "Default")
      (node (ref "D3") (pin "1") (pinfunction "A_1") (pintype "passive"))
      (node (ref "R35") (pin "1") (pinfunction "1_1") (pintype "passive"))
      (node (ref "R45") (pin "1") (pinfunction "1_1") (pintype "passive"))
      (node (ref "SV2") (pin "1") (pinfunction "1_1") (pintype "passive"))
    )
    (net (code "68") (name "VCC_LADEGERÄT_CONNECT") (class "Default")
      (node (ref "IC2") (pin "16") (pinfunction "(OC2)PD7_16") (pintype "bidirectional"))
      (node (ref "R42") (pin "1") (pinfunction "1_1") (pintype "passive"))
      (node (ref "T6") (pin "3") (pinfunction "C_3") (pintype "passive"))
    )
    (net (code "69") (name "VEPOTI") (class "Default")
      (node (ref "IC2") (pin "34") (pinfunction "(ADC3)PA3_34") (pintype "bidirectional"))
      (node (ref "R27") (pin "1") (pinfunction "1_1") (pintype "passive"))
      (node (ref "R28") (pin "2") (pinfunction "2_2") (pintype "passive"))
    )
    (net (code "70") (name "VOUT") (class "Default")
      (node (ref "C18") (pin "+") (pinfunction "+_+") (pintype "passive"))
      (node (ref "C19") (pin "+") (pinfunction "+_+") (pintype "passive"))
      (node (ref "C20") (pin "1") (pinfunction "1_1") (pintype "passive"))
      (node (ref "C29") (pin "1") (pinfunction "1_1") (pintype "passive"))
      (node (ref "D4") (pin "C") (pinfunction "C_C") (pintype "passive"))
      (node (ref "D5") (pin "A") (pinfunction "A_A") (pintype "passive"))
      (node (ref "IC6") (pin "7") (pinfunction "VOUT_7") (pintype "power_in"))
      (node (ref "R34") (pin "2") (pinfunction "2_2") (pintype "passive"))
    )
    (net (code "71") (name "WD_MODE") (class "Default")
      (node (ref "IC1") (pin "3") (pinfunction "MODE_3") (pintype "bidirectional"))
      (node (ref "IC2") (pin "9") (pinfunction "(RXD)PD0_9") (pintype "bidirectional"))
      (node (ref "R3") (pin "1") (pinfunction "1_1") (pintype "passive"))
    )
    (net (code "72") (name "WD_TRIGGER") (class "Default")
      (node (ref "IC1") (pin "2") (pinfunction "TRIGGER_2") (pintype "bidirectional"))
      (node (ref "IC2") (pin "15") (pinfunction "(ICP)PD6_15") (pintype "bidirectional"))
      (node (ref "R4") (pin "1") (pinfunction "1_1") (pintype "passive"))
    )
    (net (code "73") (name "unconnected-(IC1-ENA-Pad4)") (class "Default")
      (node (ref "IC1") (pin "4") (pinfunction "ENA_4") (pintype "bidirectional"))
    )
    (net (code "74") (name "unconnected-(IC5-NC1-Pad1)") (class "Default")
      (node (ref "IC5") (pin "1") (pinfunction "NC1_1") (pintype "no_connect"))
    )
    (net (code "75") (name "unconnected-(IC5-NC2-Pad8)") (class "Default")
      (node (ref "IC5") (pin "8") (pinfunction "NC2_8") (pintype "no_connect"))
    )
    (net (code "76") (name "unconnected-(IC6-PGOOD-Pad6)") (class "Default")
      (node (ref "IC6") (pin "6") (pinfunction "PGOOD_6") (pintype "output"))
    )
    (net (code "77") (name "unconnected-(S1-S-Pad3)") (class "Default")
      (node (ref "S1") (pin "3") (pinfunction "S_3") (pintype "passive"))
    )
    (net (code "78") (name "unconnected-(X1H-S-Pad7)") (class "Default")
      (node (ref "X1") (pin "7") (pinfunction "S_7") (pintype "passive"))
    )
    (net (code "79") (name "unconnected-(X1I-S-Pad8)") (class "Default")
      (node (ref "X1") (pin "8") (pinfunction "S_8") (pintype "passive"))
    )
    (net (code "80") (name "{slash}RESET&WATCHDOG") (class "Default")
      (node (ref "IC2") (pin "4") (pinfunction "RESET_4") (pintype "input"))
      (node (ref "R1") (pin "1") (pinfunction "1_1") (pintype "passive"))
      (node (ref "R5") (pin "2") (pinfunction "2_2") (pintype "passive"))
    )
  )
)
